# ft2232h-breakout.net
KiCad netlist of a schematic drawn in EAGLE
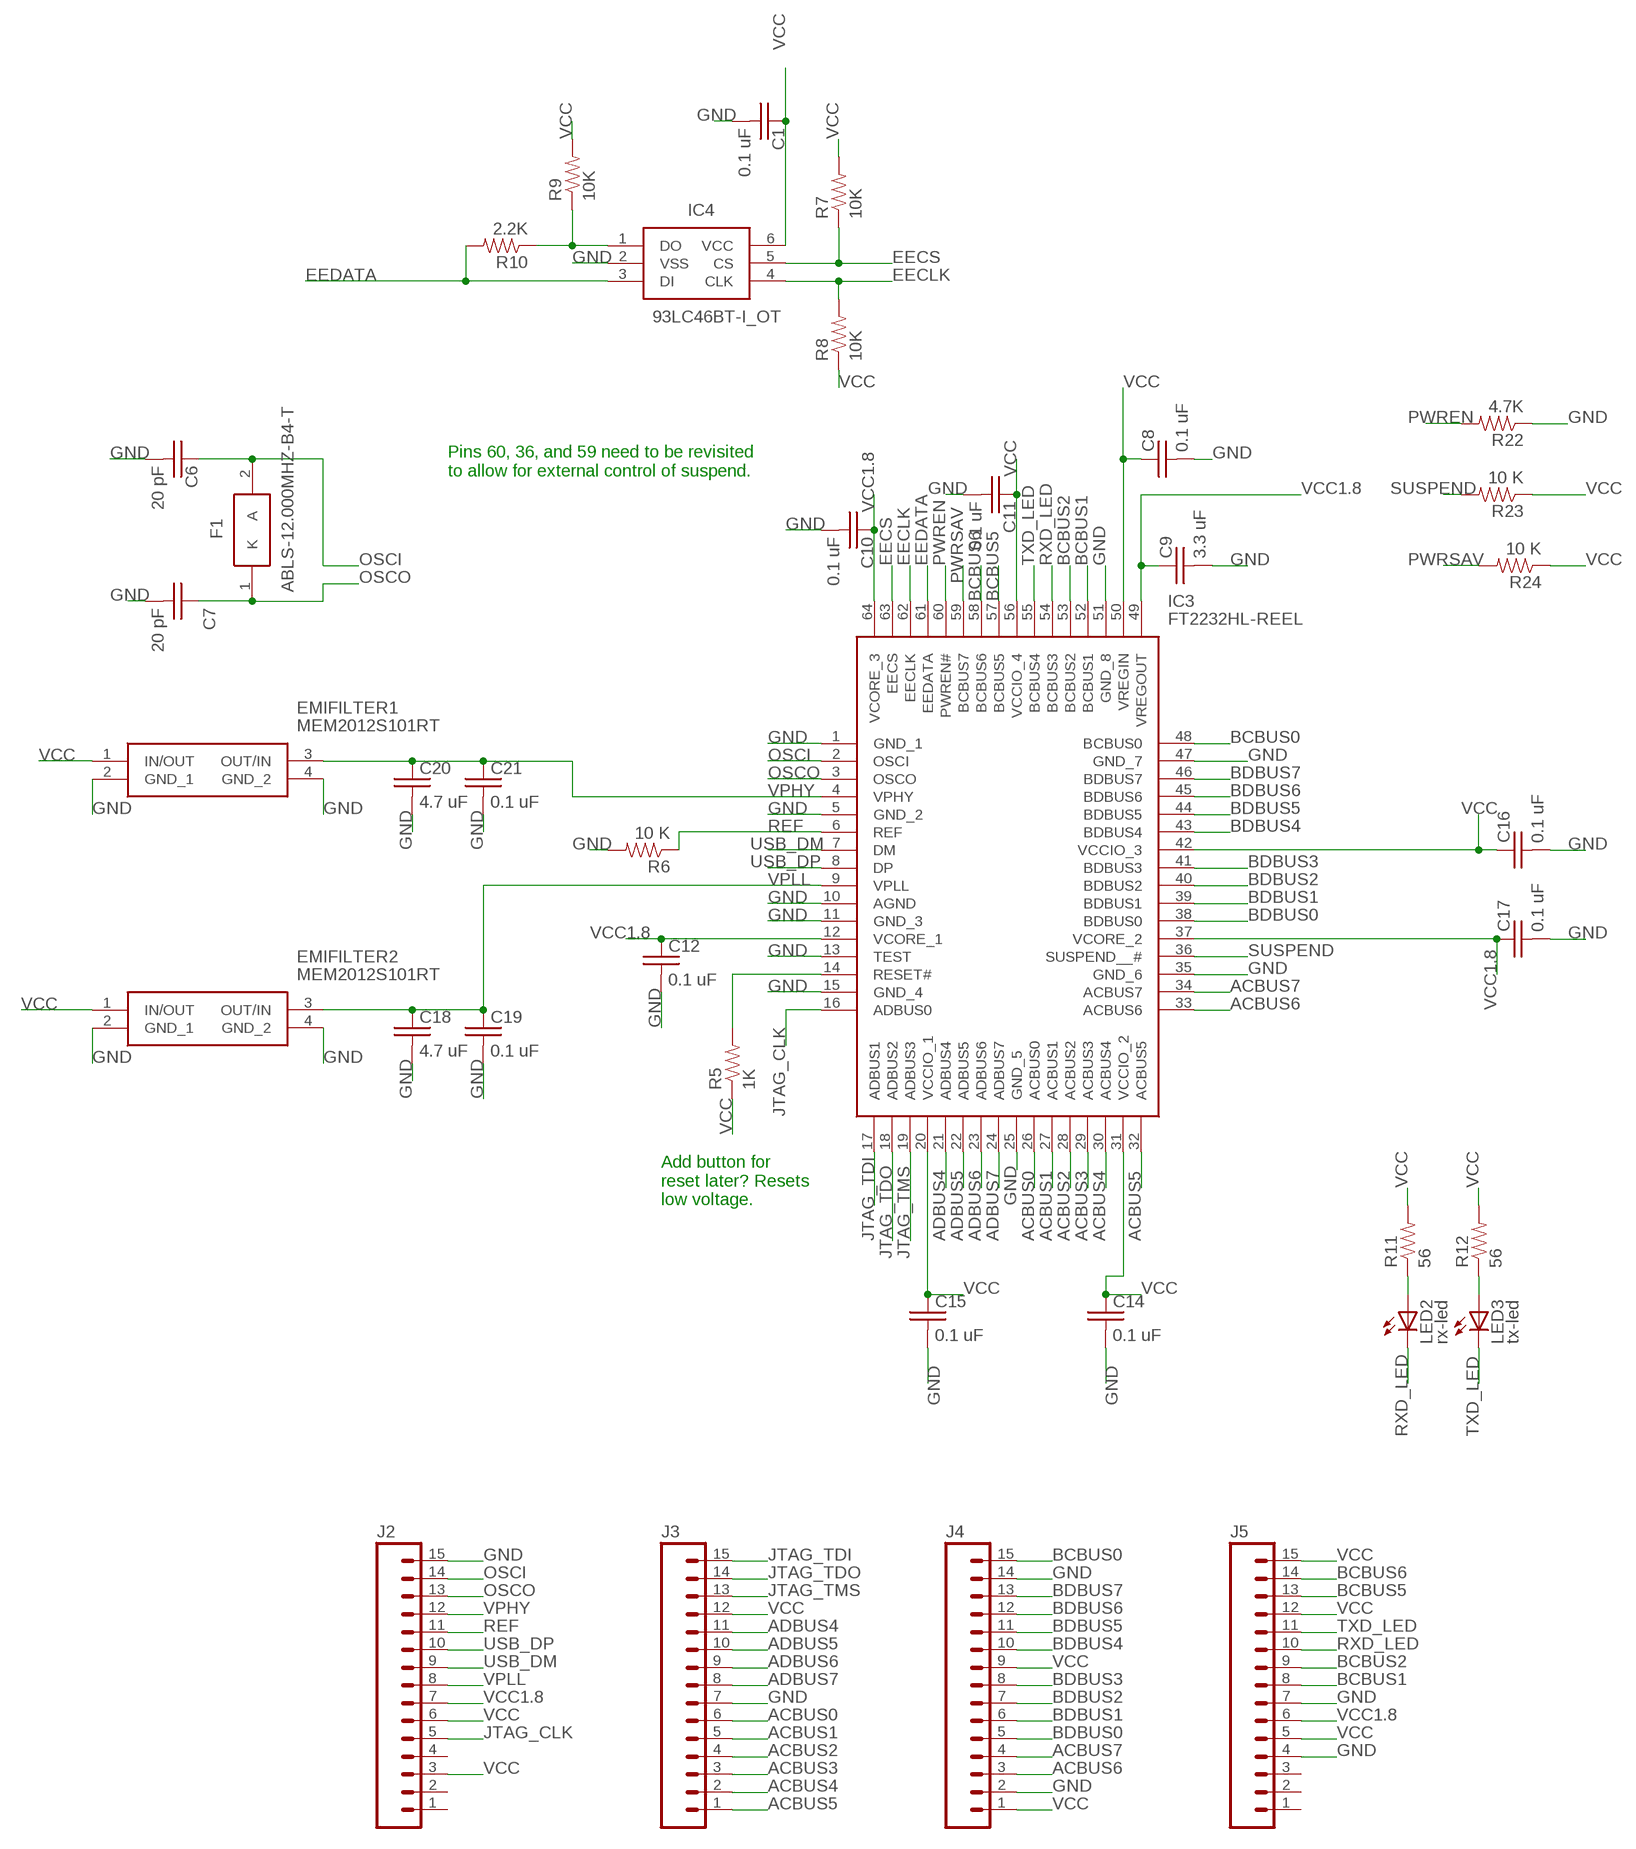
[diagram p0: schematic, sheet 1]
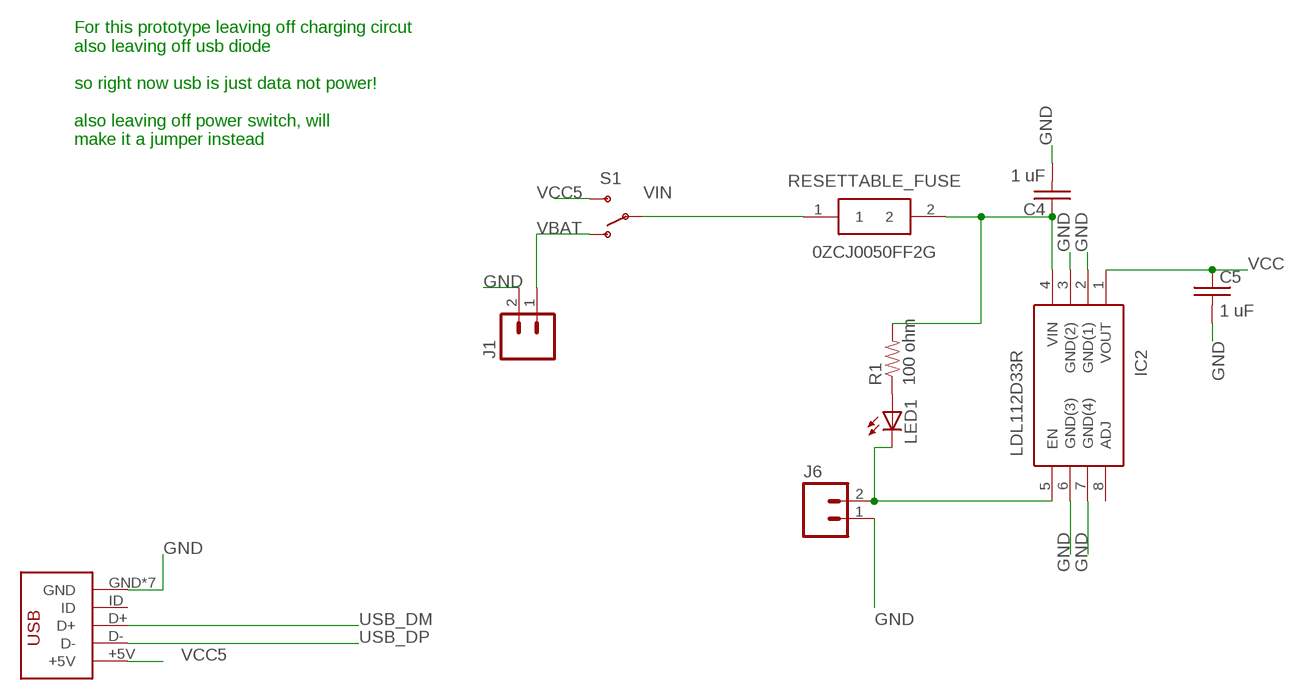
[diagram p1: schematic, sheet 2]

(export (version "E")
  (design (tool "Eeschema 10.0.6"))
  (components
    (comp (ref "C4")
      (value "1 uF")
      (footprint "eagle-import:C0805")
      (libsource (lib "eagle-import") (part "C-USC0805"))
    )
    (comp (ref "C5")
      (value "1 uF")
      (footprint "eagle-import:C0805")
      (libsource (lib "eagle-import") (part "C-USC0805"))
    )
    (comp (ref "IC2")
      (value "LDL112D33R")
      (footprint "eagle-import:SOIC127P600X175-8N")
      (libsource (lib "eagle-import") (part "LDL112D33R"))
    )
    (comp (ref "J1")
      (value "M02PTH")
      (footprint "eagle-import:1X02")
      (libsource (lib "eagle-import") (part "M02PTH"))
    )
    (comp (ref "J6")
      (value "M02PTH")
      (footprint "eagle-import:1X02")
      (libsource (lib "eagle-import") (part "M02PTH"))
    )
    (comp (ref "LED1")
      (value "LED3MM")
      (footprint "eagle-import:LED3MM")
      (libsource (lib "eagle-import") (part "LED3MM"))
    )
    (comp (ref "R1")
      (value "100 ohm")
      (footprint "eagle-import:AXIAL-0.3-KIT")
      (libsource (lib "eagle-import") (part "RESISTORKIT"))
    )
    (comp (ref "RESETTABLE_FUSE")
      (value "0ZCJ0050FF2G")
      (footprint "eagle-import:FUSC3216X55N")
      (libsource (lib "eagle-import") (part "0ZCJ0050FF2G"))
    )
    (comp (ref "S1")
      (value "SWITCH-SPSTPTH")
      (footprint "eagle-import:SWITCH-SPDT")
      (libsource (lib "eagle-import") (part "SWITCH-SPSTPTH"))
    )
    (comp (ref "U$2")
      (value "DX4R005JJ2DX4R005JJ2")
      (footprint "eagle-import:DX4R005JJ2")
      (libsource (lib "eagle-import") (part "DX4R005JJ2DX4R005JJ2"))
    )
    (comp (ref "C1")
      (value "0.1 uF")
      (footprint "eagle-import:C0805")
      (libsource (lib "eagle-import") (part "C-USC0805"))
    )
    (comp (ref "C6")
      (value "20 pF")
      (footprint "eagle-import:C0805")
      (libsource (lib "eagle-import") (part "C-USC0805"))
    )
    (comp (ref "C7")
      (value "20 pF")
      (footprint "eagle-import:C0805")
      (libsource (lib "eagle-import") (part "C-USC0805"))
    )
    (comp (ref "C8")
      (value "0.1 uF")
      (footprint "eagle-import:C0805")
      (libsource (lib "eagle-import") (part "C-USC0805"))
    )
    (comp (ref "C9")
      (value "3.3 uF")
      (footprint "eagle-import:C0805")
      (libsource (lib "eagle-import") (part "C-USC0805"))
    )
    (comp (ref "C10")
      (value "0.1 uF")
      (footprint "eagle-import:C0805")
      (libsource (lib "eagle-import") (part "C-USC0805"))
    )
    (comp (ref "C11")
      (value "0.1 uF")
      (footprint "eagle-import:C0805")
      (libsource (lib "eagle-import") (part "C-USC0805"))
    )
    (comp (ref "C12")
      (value "0.1 uF")
      (footprint "eagle-import:C0805")
      (libsource (lib "eagle-import") (part "C-USC0805"))
    )
    (comp (ref "C14")
      (value "0.1 uF")
      (footprint "eagle-import:C0805")
      (libsource (lib "eagle-import") (part "C-USC0805"))
    )
    (comp (ref "C15")
      (value "0.1 uF")
      (footprint "eagle-import:C0805")
      (libsource (lib "eagle-import") (part "C-USC0805"))
    )
    (comp (ref "C16")
      (value "0.1 uF")
      (footprint "eagle-import:C0805")
      (libsource (lib "eagle-import") (part "C-USC0805"))
    )
    (comp (ref "C17")
      (value "0.1 uF")
      (footprint "eagle-import:C0805")
      (libsource (lib "eagle-import") (part "C-USC0805"))
    )
    (comp (ref "C18")
      (value "4.7 uF")
      (footprint "eagle-import:C0805")
      (libsource (lib "eagle-import") (part "C-USC0805"))
    )
    (comp (ref "C19")
      (value "0.1 uF")
      (footprint "eagle-import:C0805")
      (libsource (lib "eagle-import") (part "C-USC0805"))
    )
    (comp (ref "C20")
      (value "4.7 uF")
      (footprint "eagle-import:C0805")
      (libsource (lib "eagle-import") (part "C-USC0805"))
    )
    (comp (ref "C21")
      (value "0.1 uF")
      (footprint "eagle-import:C0805")
      (libsource (lib "eagle-import") (part "C-USC0805"))
    )
    (comp (ref "EMIFILTER1")
      (value "MEM2012S101RT")
      (footprint "eagle-import:MEM2012S101RT")
      (libsource (lib "eagle-import") (part "MEM2012S101RT"))
    )
    (comp (ref "EMIFILTER2")
      (value "MEM2012S101RT")
      (footprint "eagle-import:MEM2012S101RT")
      (libsource (lib "eagle-import") (part "MEM2012S101RT"))
    )
    (comp (ref "F1")
      (value "ABLS-12.000MHZ-B4-T")
      (footprint "eagle-import:HC_49US-(AT49)_1")
      (fields
        (field (name "MOUSER_PART_NUMBER") "815-ABLS-12.0M-T")
        (field (name "RS_PART_NUMBER") "1710207")
      )
      (libsource (lib "eagle-import") (part "ABLS-12.000MHZ-B4-T"))
    )
    (comp (ref "IC3")
      (value "FT2232HL-REEL")
      (footprint "eagle-import:QFP50P1200X1200X160-64N")
      (fields (field (name "MOUSER_PART_NUMBER") "895-FT2232HL"))
      (libsource (lib "eagle-import") (part "FT2232HL-REEL"))
    )
    (comp (ref "IC4")
      (value "93LC46BT-I_OT")
      (footprint "eagle-import:SOT95P270X145-6N")
      (fields
        (field (name "MANUFACTURER_PART_NUMBER") "93LC46BT-I/OT")
        (field (name "MOUSER_PART_NUMBER") "579-93LC46BT-I/OT")
      )
      (libsource (lib "eagle-import") (part "93LC46BT-I_OT"))
    )
    (comp (ref "J2")
      (value "M15")
      (footprint "eagle-import:1X15")
      (libsource (lib "eagle-import") (part "M15"))
    )
    (comp (ref "J3")
      (value "M15")
      (footprint "eagle-import:1X15")
      (libsource (lib "eagle-import") (part "M15"))
    )
    (comp (ref "J4")
      (value "M15")
      (footprint "eagle-import:1X15")
      (libsource (lib "eagle-import") (part "M15"))
    )
    (comp (ref "J5")
      (value "M15")
      (footprint "eagle-import:1X15")
      (libsource (lib "eagle-import") (part "M15"))
    )
    (comp (ref "LED2")
      (value "rx-led")
      (footprint "eagle-import:LED3MM")
      (libsource (lib "eagle-import") (part "LED3MM"))
    )
    (comp (ref "LED3")
      (value "tx-led")
      (footprint "eagle-import:LED3MM")
      (libsource (lib "eagle-import") (part "LED3MM"))
    )
    (comp (ref "R5")
      (value "1K")
      (footprint "eagle-import:0805")
      (libsource (lib "eagle-import") (part "RESISTOR0805-RES"))
    )
    (comp (ref "R6")
      (value "10 K")
      (footprint "eagle-import:0805")
      (libsource (lib "eagle-import") (part "RESISTOR0805-RES"))
    )
    (comp (ref "R7")
      (value "10K")
      (footprint "eagle-import:0805")
      (libsource (lib "eagle-import") (part "RESISTOR0805-RES"))
    )
    (comp (ref "R8")
      (value "10K")
      (footprint "eagle-import:0805")
      (libsource (lib "eagle-import") (part "RESISTOR0805-RES"))
    )
    (comp (ref "R9")
      (value "10K")
      (footprint "eagle-import:0805")
      (libsource (lib "eagle-import") (part "RESISTOR0805-RES"))
    )
    (comp (ref "R10")
      (value "2.2K")
      (footprint "eagle-import:0805")
      (libsource (lib "eagle-import") (part "RESISTOR0805-RES"))
    )
    (comp (ref "R11")
      (value "56")
      (footprint "eagle-import:0805")
      (libsource (lib "eagle-import") (part "RESISTOR0805-RES"))
    )
    (comp (ref "R12")
      (value "56")
      (footprint "eagle-import:0805")
      (libsource (lib "eagle-import") (part "RESISTOR0805-RES"))
    )
    (comp (ref "R22")
      (value "4.7K")
      (footprint "eagle-import:0805")
      (libsource (lib "eagle-import") (part "RESISTOR0805-RES"))
    )
    (comp (ref "R23")
      (value "10 K")
      (footprint "eagle-import:0805")
      (libsource (lib "eagle-import") (part "RESISTOR0805-RES"))
    )
    (comp (ref "R24")
      (value "10 K")
      (footprint "eagle-import:0805")
      (libsource (lib "eagle-import") (part "RESISTOR0805-RES"))
    )
  )
  (nets
    (net (code "1") (name "ACBUS0") (class "Default")
      (node (ref "IC3") (pin "26") (pinfunction "ACBUS0_26") (pintype "bidirectional"))
      (node (ref "J3") (pin "6") (pinfunction "6_6") (pintype "passive"))
    )
    (net (code "2") (name "ACBUS1") (class "Default")
      (node (ref "IC3") (pin "27") (pinfunction "ACBUS1_27") (pintype "bidirectional"))
      (node (ref "J3") (pin "5") (pinfunction "5_5") (pintype "passive"))
    )
    (net (code "3") (name "ACBUS2") (class "Default")
      (node (ref "IC3") (pin "28") (pinfunction "ACBUS2_28") (pintype "bidirectional"))
      (node (ref "J3") (pin "4") (pinfunction "4_4") (pintype "passive"))
    )
    (net (code "4") (name "ACBUS3") (class "Default")
      (node (ref "IC3") (pin "29") (pinfunction "ACBUS3_29") (pintype "bidirectional"))
      (node (ref "J3") (pin "3") (pinfunction "3_3") (pintype "passive"))
    )
    (net (code "5") (name "ACBUS4") (class "Default")
      (node (ref "IC3") (pin "30") (pinfunction "ACBUS4_30") (pintype "bidirectional"))
      (node (ref "J3") (pin "2") (pinfunction "2_2") (pintype "passive"))
    )
    (net (code "6") (name "ACBUS5") (class "Default")
      (node (ref "IC3") (pin "32") (pinfunction "ACBUS5_32") (pintype "bidirectional"))
      (node (ref "J3") (pin "1") (pinfunction "1_1") (pintype "passive"))
    )
    (net (code "7") (name "ACBUS6") (class "Default")
      (node (ref "IC3") (pin "33") (pinfunction "ACBUS6_33") (pintype "bidirectional"))
      (node (ref "J4") (pin "3") (pinfunction "3_3") (pintype "passive"))
    )
    (net (code "8") (name "ACBUS7") (class "Default")
      (node (ref "IC3") (pin "34") (pinfunction "ACBUS7_34") (pintype "bidirectional"))
      (node (ref "J4") (pin "4") (pinfunction "4_4") (pintype "passive"))
    )
    (net (code "9") (name "ADBUS4") (class "Default")
      (node (ref "IC3") (pin "21") (pinfunction "ADBUS4_21") (pintype "bidirectional"))
      (node (ref "J3") (pin "11") (pinfunction "11_11") (pintype "passive"))
    )
    (net (code "10") (name "ADBUS5") (class "Default")
      (node (ref "IC3") (pin "22") (pinfunction "ADBUS5_22") (pintype "bidirectional"))
      (node (ref "J3") (pin "10") (pinfunction "10_10") (pintype "passive"))
    )
    (net (code "11") (name "ADBUS6") (class "Default")
      (node (ref "IC3") (pin "23") (pinfunction "ADBUS6_23") (pintype "bidirectional"))
      (node (ref "J3") (pin "9") (pinfunction "9_9") (pintype "passive"))
    )
    (net (code "12") (name "ADBUS7") (class "Default")
      (node (ref "IC3") (pin "24") (pinfunction "ADBUS7_24") (pintype "bidirectional"))
      (node (ref "J3") (pin "8") (pinfunction "8_8") (pintype "passive"))
    )
    (net (code "13") (name "BCBUS0") (class "Default")
      (node (ref "IC3") (pin "48") (pinfunction "BCBUS0_48") (pintype "bidirectional"))
      (node (ref "J4") (pin "15") (pinfunction "15_15") (pintype "passive"))
    )
    (net (code "14") (name "BCBUS1") (class "Default")
      (node (ref "IC3") (pin "52") (pinfunction "BCBUS1_52") (pintype "bidirectional"))
      (node (ref "J5") (pin "8") (pinfunction "8_8") (pintype "passive"))
    )
    (net (code "15") (name "BCBUS2") (class "Default")
      (node (ref "IC3") (pin "53") (pinfunction "BCBUS2_53") (pintype "bidirectional"))
      (node (ref "J5") (pin "9") (pinfunction "9_9") (pintype "passive"))
    )
    (net (code "16") (name "BCBUS5") (class "Default")
      (node (ref "IC3") (pin "57") (pinfunction "BCBUS5_57") (pintype "bidirectional"))
      (node (ref "J5") (pin "13") (pinfunction "13_13") (pintype "passive"))
    )
    (net (code "17") (name "BCBUS6") (class "Default")
      (node (ref "IC3") (pin "58") (pinfunction "BCBUS6_58") (pintype "bidirectional"))
      (node (ref "J5") (pin "14") (pinfunction "14_14") (pintype "passive"))
    )
    (net (code "18") (name "BDBUS0") (class "Default")
      (node (ref "IC3") (pin "38") (pinfunction "BDBUS0_38") (pintype "bidirectional"))
      (node (ref "J4") (pin "5") (pinfunction "5_5") (pintype "passive"))
    )
    (net (code "19") (name "BDBUS1") (class "Default")
      (node (ref "IC3") (pin "39") (pinfunction "BDBUS1_39") (pintype "bidirectional"))
      (node (ref "J4") (pin "6") (pinfunction "6_6") (pintype "passive"))
    )
    (net (code "20") (name "BDBUS2") (class "Default")
      (node (ref "IC3") (pin "40") (pinfunction "BDBUS2_40") (pintype "bidirectional"))
      (node (ref "J4") (pin "7") (pinfunction "7_7") (pintype "passive"))
    )
    (net (code "21") (name "BDBUS3") (class "Default")
      (node (ref "IC3") (pin "41") (pinfunction "BDBUS3_41") (pintype "bidirectional"))
      (node (ref "J4") (pin "8") (pinfunction "8_8") (pintype "passive"))
    )
    (net (code "22") (name "BDBUS4") (class "Default")
      (node (ref "IC3") (pin "43") (pinfunction "BDBUS4_43") (pintype "bidirectional"))
      (node (ref "J4") (pin "10") (pinfunction "10_10") (pintype "passive"))
    )
    (net (code "23") (name "BDBUS5") (class "Default")
      (node (ref "IC3") (pin "44") (pinfunction "BDBUS5_44") (pintype "bidirectional"))
      (node (ref "J4") (pin "11") (pinfunction "11_11") (pintype "passive"))
    )
    (net (code "24") (name "BDBUS6") (class "Default")
      (node (ref "IC3") (pin "45") (pinfunction "BDBUS6_45") (pintype "bidirectional"))
      (node (ref "J4") (pin "12") (pinfunction "12_12") (pintype "passive"))
    )
    (net (code "25") (name "BDBUS7") (class "Default")
      (node (ref "IC3") (pin "46") (pinfunction "BDBUS7_46") (pintype "bidirectional"))
      (node (ref "J4") (pin "13") (pinfunction "13_13") (pintype "passive"))
    )
    (net (code "26") (name "EECLK") (class "Default")
      (node (ref "IC3") (pin "62") (pinfunction "EECLK_62") (pintype "bidirectional"))
      (node (ref "IC4") (pin "4") (pinfunction "CLK_4") (pintype "input"))
      (node (ref "R8") (pin "2") (pinfunction "2_2") (pintype "passive"))
    )
    (net (code "27") (name "EECS") (class "Default")
      (node (ref "IC3") (pin "63") (pinfunction "EECS_63") (pintype "bidirectional"))
      (node (ref "IC4") (pin "5") (pinfunction "CS_5") (pintype "input"))
      (node (ref "R7") (pin "1") (pinfunction "1_1") (pintype "passive"))
    )
    (net (code "28") (name "EEDATA") (class "Default")
      (node (ref "IC3") (pin "61") (pinfunction "EEDATA_61") (pintype "bidirectional"))
      (node (ref "IC4") (pin "3") (pinfunction "DI_3") (pintype "bidirectional"))
      (node (ref "R10") (pin "2") (pinfunction "2_2") (pintype "passive"))
    )
    (net (code "29") (name "GND") (class "Default")
      (node (ref "C1") (pin "2") (pinfunction "2_2") (pintype "passive"))
      (node (ref "C10") (pin "2") (pinfunction "2_2") (pintype "passive"))
      (node (ref "C11") (pin "2") (pinfunction "2_2") (pintype "passive"))
      (node (ref "C12") (pin "2") (pinfunction "2_2") (pintype "passive"))
      (node (ref "C14") (pin "2") (pinfunction "2_2") (pintype "passive"))
      (node (ref "C15") (pin "2") (pinfunction "2_2") (pintype "passive"))
      (node (ref "C16") (pin "2") (pinfunction "2_2") (pintype "passive"))
      (node (ref "C17") (pin "2") (pinfunction "2_2") (pintype "passive"))
      (node (ref "C18") (pin "2") (pinfunction "2_2") (pintype "passive"))
      (node (ref "C19") (pin "2") (pinfunction "2_2") (pintype "passive"))
      (node (ref "C20") (pin "2") (pinfunction "2_2") (pintype "passive"))
      (node (ref "C21") (pin "2") (pinfunction "2_2") (pintype "passive"))
      (node (ref "C4") (pin "2") (pinfunction "2_2") (pintype "passive"))
      (node (ref "C5") (pin "2") (pinfunction "2_2") (pintype "passive"))
      (node (ref "C6") (pin "2") (pinfunction "2_2") (pintype "passive"))
      (node (ref "C7") (pin "2") (pinfunction "2_2") (pintype "passive"))
      (node (ref "C8") (pin "2") (pinfunction "2_2") (pintype "passive"))
      (node (ref "C9") (pin "2") (pinfunction "2_2") (pintype "passive"))
      (node (ref "EMIFILTER1") (pin "2") (pinfunction "GND_1_2") (pintype "bidirectional"))
      (node (ref "EMIFILTER1") (pin "4") (pinfunction "GND_2_4") (pintype "bidirectional"))
      (node (ref "EMIFILTER2") (pin "2") (pinfunction "GND_1_2") (pintype "bidirectional"))
      (node (ref "EMIFILTER2") (pin "4") (pinfunction "GND_2_4") (pintype "bidirectional"))
      (node (ref "IC2") (pin "2") (pinfunction "GND(1)_2") (pintype "bidirectional"))
      (node (ref "IC2") (pin "3") (pinfunction "GND(2)_3") (pintype "bidirectional"))
      (node (ref "IC2") (pin "6") (pinfunction "GND(3)_6") (pintype "bidirectional"))
      (node (ref "IC2") (pin "7") (pinfunction "GND(4)_7") (pintype "bidirectional"))
      (node (ref "IC3") (pin "1") (pinfunction "GND_1_1") (pintype "bidirectional"))
      (node (ref "IC3") (pin "10") (pinfunction "AGND_10") (pintype "bidirectional"))
      (node (ref "IC3") (pin "11") (pinfunction "GND_3_11") (pintype "bidirectional"))
      (node (ref "IC3") (pin "13") (pinfunction "TEST_13") (pintype "bidirectional"))
      (node (ref "IC3") (pin "15") (pinfunction "GND_4_15") (pintype "bidirectional"))
      (node (ref "IC3") (pin "25") (pinfunction "GND_5_25") (pintype "bidirectional"))
      (node (ref "IC3") (pin "35") (pinfunction "GND_6_35") (pintype "bidirectional"))
      (node (ref "IC3") (pin "47") (pinfunction "GND_7_47") (pintype "bidirectional"))
      (node (ref "IC3") (pin "5") (pinfunction "GND_2_5") (pintype "bidirectional"))
      (node (ref "IC3") (pin "51") (pinfunction "GND_8_51") (pintype "bidirectional"))
      (node (ref "IC4") (pin "2") (pinfunction "VSS_2") (pintype "power_in"))
      (node (ref "J1") (pin "2") (pinfunction "2_2") (pintype "passive"))
      (node (ref "J2") (pin "15") (pinfunction "15_15") (pintype "passive"))
      (node (ref "J3") (pin "7") (pinfunction "7_7") (pintype "passive"))
      (node (ref "J4") (pin "14") (pinfunction "14_14") (pintype "passive"))
      (node (ref "J4") (pin "2") (pinfunction "2_2") (pintype "passive"))
      (node (ref "J5") (pin "4") (pinfunction "4_4") (pintype "passive"))
      (node (ref "J5") (pin "7") (pinfunction "7_7") (pintype "passive"))
      (node (ref "J6") (pin "1") (pinfunction "1_1") (pintype "passive"))
      (node (ref "R22") (pin "1") (pinfunction "1_1") (pintype "passive"))
      (node (ref "R6") (pin "2") (pinfunction "2_2") (pintype "passive"))
      (node (ref "U$2") (pin "GND") (pinfunction "GND_GND") (pintype "bidirectional"))
      (node (ref "U$2") (pin "P$10") (pinfunction "GND_P$10") (pintype "bidirectional"))
      (node (ref "U$2") (pin "P$11") (pinfunction "GND_P$11") (pintype "bidirectional"))
      (node (ref "U$2") (pin "P$6") (pinfunction "GND_P$6") (pintype "bidirectional"))
      (node (ref "U$2") (pin "P$7") (pinfunction "GND_P$7") (pintype "bidirectional"))
      (node (ref "U$2") (pin "P$8") (pinfunction "GND_P$8") (pintype "bidirectional"))
      (node (ref "U$2") (pin "P$9") (pinfunction "GND_P$9") (pintype "bidirectional"))
    )
    (net (code "30") (name "JTAG_CLK") (class "Default")
      (node (ref "IC3") (pin "16") (pinfunction "ADBUS0_16") (pintype "bidirectional"))
      (node (ref "J2") (pin "5") (pinfunction "5_5") (pintype "passive"))
    )
    (net (code "31") (name "JTAG_TDI") (class "Default")
      (node (ref "IC3") (pin "17") (pinfunction "ADBUS1_17") (pintype "bidirectional"))
      (node (ref "J3") (pin "15") (pinfunction "15_15") (pintype "passive"))
    )
    (net (code "32") (name "JTAG_TDO") (class "Default")
      (node (ref "IC3") (pin "18") (pinfunction "ADBUS2_18") (pintype "bidirectional"))
      (node (ref "J3") (pin "14") (pinfunction "14_14") (pintype "passive"))
    )
    (net (code "33") (name "JTAG_TMS") (class "Default")
      (node (ref "IC3") (pin "19") (pinfunction "ADBUS3_19") (pintype "bidirectional"))
      (node (ref "J3") (pin "13") (pinfunction "13_13") (pintype "passive"))
    )
    (net (code "34") (name "Net-(IC2-EN)") (class "Default")
      (node (ref "IC2") (pin "5") (pinfunction "EN_5") (pintype "bidirectional"))
      (node (ref "J6") (pin "2") (pinfunction "2_2") (pintype "passive"))
      (node (ref "LED1") (pin "K") (pinfunction "C_K") (pintype "output"))
    )
    (net (code "35") (name "Net-(IC2-VIN)") (class "Default")
      (node (ref "C4") (pin "1") (pinfunction "1_1") (pintype "passive"))
      (node (ref "IC2") (pin "4") (pinfunction "VIN_4") (pintype "bidirectional"))
      (node (ref "R1") (pin "P$2") (pinfunction "2_P$2") (pintype "passive"))
      (node (ref "RESETTABLE_FUSE") (pin "2") (pinfunction "2_2") (pintype "passive"))
    )
    (net (code "36") (name "Net-(IC3-RESET#)") (class "Default")
      (node (ref "IC3") (pin "14") (pinfunction "RESET#_14") (pintype "bidirectional"))
      (node (ref "R5") (pin "2") (pinfunction "2_2") (pintype "passive"))
    )
    (net (code "37") (name "Net-(IC4-DO)") (class "Default")
      (node (ref "IC4") (pin "1") (pinfunction "DO_1") (pintype "bidirectional"))
      (node (ref "R10") (pin "1") (pinfunction "1_1") (pintype "passive"))
      (node (ref "R9") (pin "1") (pinfunction "1_1") (pintype "passive"))
    )
    (net (code "38") (name "Net-(LED2-PadA)") (class "Default")
      (node (ref "LED2") (pin "A") (pinfunction "A_A") (pintype "input"))
      (node (ref "R11") (pin "1") (pinfunction "1_1") (pintype "passive"))
    )
    (net (code "39") (name "Net-(LED3-PadA)") (class "Default")
      (node (ref "LED3") (pin "A") (pinfunction "A_A") (pintype "input"))
      (node (ref "R12") (pin "1") (pinfunction "1_1") (pintype "passive"))
    )
    (net (code "40") (name "Net-(R1-1)") (class "Default")
      (node (ref "LED1") (pin "A") (pinfunction "A_A") (pintype "input"))
      (node (ref "R1") (pin "P$1") (pinfunction "1_P$1") (pintype "passive"))
    )
    (net (code "41") (name "OSCI") (class "Default")
      (node (ref "C6") (pin "1") (pinfunction "1_1") (pintype "passive"))
      (node (ref "F1") (pin "2") (pinfunction "A_2") (pintype "bidirectional"))
      (node (ref "IC3") (pin "2") (pinfunction "OSCI_2") (pintype "bidirectional"))
      (node (ref "J2") (pin "14") (pinfunction "14_14") (pintype "passive"))
    )
    (net (code "42") (name "OSCO") (class "Default")
      (node (ref "C7") (pin "1") (pinfunction "1_1") (pintype "passive"))
      (node (ref "F1") (pin "1") (pinfunction "K_1") (pintype "bidirectional"))
      (node (ref "IC3") (pin "3") (pinfunction "OSCO_3") (pintype "bidirectional"))
      (node (ref "J2") (pin "13") (pinfunction "13_13") (pintype "passive"))
    )
    (net (code "43") (name "PWREN") (class "Default")
      (node (ref "IC3") (pin "60") (pinfunction "PWREN#_60") (pintype "bidirectional"))
      (node (ref "R22") (pin "2") (pinfunction "2_2") (pintype "passive"))
    )
    (net (code "44") (name "PWRSAV") (class "Default")
      (node (ref "IC3") (pin "59") (pinfunction "BCBUS7_59") (pintype "bidirectional"))
      (node (ref "R24") (pin "2") (pinfunction "2_2") (pintype "passive"))
    )
    (net (code "45") (name "REF") (class "Default")
      (node (ref "IC3") (pin "6") (pinfunction "REF_6") (pintype "bidirectional"))
      (node (ref "J2") (pin "11") (pinfunction "11_11") (pintype "passive"))
      (node (ref "R6") (pin "1") (pinfunction "1_1") (pintype "passive"))
    )
    (net (code "46") (name "RXD_LED") (class "Default")
      (node (ref "IC3") (pin "54") (pinfunction "BCBUS3_54") (pintype "bidirectional"))
      (node (ref "J5") (pin "10") (pinfunction "10_10") (pintype "passive"))
      (node (ref "LED2") (pin "K") (pinfunction "C_K") (pintype "output"))
    )
    (net (code "47") (name "SUSPEND") (class "Default")
      (node (ref "IC3") (pin "36") (pinfunction "SUSPEND__#_36") (pintype "bidirectional"))
      (node (ref "R23") (pin "2") (pinfunction "2_2") (pintype "passive"))
    )
    (net (code "48") (name "TXD_LED") (class "Default")
      (node (ref "IC3") (pin "55") (pinfunction "BCBUS4_55") (pintype "bidirectional"))
      (node (ref "J5") (pin "11") (pinfunction "11_11") (pintype "passive"))
      (node (ref "LED3") (pin "K") (pinfunction "C_K") (pintype "output"))
    )
    (net (code "49") (name "USB_DM") (class "Default")
      (node (ref "IC3") (pin "7") (pinfunction "DM_7") (pintype "bidirectional"))
      (node (ref "J2") (pin "9") (pinfunction "9_9") (pintype "passive"))
      (node (ref "U$2") (pin "D+") (pinfunction "D+_D+") (pintype "bidirectional"))
    )
    (net (code "50") (name "USB_DP") (class "Default")
      (node (ref "IC3") (pin "8") (pinfunction "DP_8") (pintype "bidirectional"))
      (node (ref "J2") (pin "10") (pinfunction "10_10") (pintype "passive"))
      (node (ref "U$2") (pin "D-") (pinfunction "D-_D-") (pintype "bidirectional"))
    )
    (net (code "51") (name "VBAT") (class "Default")
      (node (ref "J1") (pin "1") (pinfunction "1_1") (pintype "passive"))
      (node (ref "S1") (pin "1") (pinfunction "O_1") (pintype "passive"))
    )
    (net (code "52") (name "VCC") (class "Default")
      (node (ref "C1") (pin "1") (pinfunction "1_1") (pintype "passive"))
      (node (ref "C11") (pin "1") (pinfunction "1_1") (pintype "passive"))
      (node (ref "C14") (pin "1") (pinfunction "1_1") (pintype "passive"))
      (node (ref "C15") (pin "1") (pinfunction "1_1") (pintype "passive"))
      (node (ref "C16") (pin "1") (pinfunction "1_1") (pintype "passive"))
      (node (ref "C5") (pin "1") (pinfunction "1_1") (pintype "passive"))
      (node (ref "C8") (pin "1") (pinfunction "1_1") (pintype "passive"))
      (node (ref "EMIFILTER1") (pin "1") (pinfunction "IN/OUT_1") (pintype "bidirectional"))
      (node (ref "EMIFILTER2") (pin "1") (pinfunction "IN/OUT_1") (pintype "bidirectional"))
      (node (ref "IC2") (pin "1") (pinfunction "VOUT_1") (pintype "bidirectional"))
      (node (ref "IC3") (pin "20") (pinfunction "VCCIO_1_20") (pintype "bidirectional"))
      (node (ref "IC3") (pin "31") (pinfunction "VCCIO_2_31") (pintype "bidirectional"))
      (node (ref "IC3") (pin "42") (pinfunction "VCCIO_3_42") (pintype "bidirectional"))
      (node (ref "IC3") (pin "50") (pinfunction "VREGIN_50") (pintype "bidirectional"))
      (node (ref "IC3") (pin "56") (pinfunction "VCCIO_4_56") (pintype "bidirectional"))
      (node (ref "IC4") (pin "6") (pinfunction "VCC_6") (pintype "power_in"))
      (node (ref "J2") (pin "3") (pinfunction "3_3") (pintype "passive"))
      (node (ref "J2") (pin "6") (pinfunction "6_6") (pintype "passive"))
      (node (ref "J3") (pin "12") (pinfunction "12_12") (pintype "passive"))
      (node (ref "J4") (pin "1") (pinfunction "1_1") (pintype "passive"))
      (node (ref "J4") (pin "9") (pinfunction "9_9") (pintype "passive"))
      (node (ref "J5") (pin "12") (pinfunction "12_12") (pintype "passive"))
      (node (ref "J5") (pin "15") (pinfunction "15_15") (pintype "passive"))
      (node (ref "J5") (pin "5") (pinfunction "5_5") (pintype "passive"))
      (node (ref "R11") (pin "2") (pinfunction "2_2") (pintype "passive"))
      (node (ref "R12") (pin "2") (pinfunction "2_2") (pintype "passive"))
      (node (ref "R23") (pin "1") (pinfunction "1_1") (pintype "passive"))
      (node (ref "R24") (pin "1") (pinfunction "1_1") (pintype "passive"))
      (node (ref "R5") (pin "1") (pinfunction "1_1") (pintype "passive"))
      (node (ref "R7") (pin "2") (pinfunction "2_2") (pintype "passive"))
      (node (ref "R8") (pin "1") (pinfunction "1_1") (pintype "passive"))
      (node (ref "R9") (pin "2") (pinfunction "2_2") (pintype "passive"))
    )
    (net (code "53") (name "VCC1.8") (class "Default")
      (node (ref "C10") (pin "1") (pinfunction "1_1") (pintype "passive"))
      (node (ref "C12") (pin "1") (pinfunction "1_1") (pintype "passive"))
      (node (ref "C17") (pin "1") (pinfunction "1_1") (pintype "passive"))
      (node (ref "C9") (pin "1") (pinfunction "1_1") (pintype "passive"))
      (node (ref "IC3") (pin "12") (pinfunction "VCORE_1_12") (pintype "bidirectional"))
      (node (ref "IC3") (pin "37") (pinfunction "VCORE_2_37") (pintype "bidirectional"))
      (node (ref "IC3") (pin "49") (pinfunction "VREGOUT_49") (pintype "bidirectional"))
      (node (ref "IC3") (pin "64") (pinfunction "VCORE_3_64") (pintype "bidirectional"))
      (node (ref "J2") (pin "7") (pinfunction "7_7") (pintype "passive"))
      (node (ref "J5") (pin "6") (pinfunction "6_6") (pintype "passive"))
    )
    (net (code "54") (name "VCC5") (class "Default")
      (node (ref "S1") (pin "3") (pinfunction "S_3") (pintype "passive"))
      (node (ref "U$2") (pin "+5V") (pinfunction "+5V_+5V") (pintype "bidirectional"))
    )
    (net (code "55") (name "VIN") (class "Default")
      (node (ref "RESETTABLE_FUSE") (pin "1") (pinfunction "1_1") (pintype "passive"))
      (node (ref "S1") (pin "2") (pinfunction "P_2") (pintype "passive"))
    )
    (net (code "56") (name "VPHY") (class "Default")
      (node (ref "C20") (pin "1") (pinfunction "1_1") (pintype "passive"))
      (node (ref "C21") (pin "1") (pinfunction "1_1") (pintype "passive"))
      (node (ref "EMIFILTER1") (pin "3") (pinfunction "OUT/IN_3") (pintype "bidirectional"))
      (node (ref "IC3") (pin "4") (pinfunction "VPHY_4") (pintype "bidirectional"))
      (node (ref "J2") (pin "12") (pinfunction "12_12") (pintype "passive"))
    )
    (net (code "57") (name "VPLL") (class "Default")
      (node (ref "C18") (pin "1") (pinfunction "1_1") (pintype "passive"))
      (node (ref "C19") (pin "1") (pinfunction "1_1") (pintype "passive"))
      (node (ref "EMIFILTER2") (pin "3") (pinfunction "OUT/IN_3") (pintype "bidirectional"))
      (node (ref "IC3") (pin "9") (pinfunction "VPLL_9") (pintype "bidirectional"))
      (node (ref "J2") (pin "8") (pinfunction "8_8") (pintype "passive"))
    )
    (net (code "58") (name "unconnected-(IC2-ADJ-Pad8)") (class "Default")
      (node (ref "IC2") (pin "8") (pinfunction "ADJ_8") (pintype "bidirectional"))
    )
    (net (code "59") (name "unconnected-(J2-Pad1)") (class "Default")
      (node (ref "J2") (pin "1") (pinfunction "1_1") (pintype "passive"))
    )
    (net (code "60") (name "unconnected-(J2-Pad2)") (class "Default")
      (node (ref "J2") (pin "2") (pinfunction "2_2") (pintype "passive"))
    )
    (net (code "61") (name "unconnected-(J2-Pad4)") (class "Default")
      (node (ref "J2") (pin "4") (pinfunction "4_4") (pintype "passive"))
    )
    (net (code "62") (name "unconnected-(J5-Pad1)") (class "Default")
      (node (ref "J5") (pin "1") (pinfunction "1_1") (pintype "passive"))
    )
    (net (code "63") (name "unconnected-(J5-Pad2)") (class "Default")
      (node (ref "J5") (pin "2") (pinfunction "2_2") (pintype "passive"))
    )
    (net (code "64") (name "unconnected-(J5-Pad3)") (class "Default")
      (node (ref "J5") (pin "3") (pinfunction "3_3") (pintype "passive"))
    )
    (net (code "65") (name "unconnected-(U$2-PadID)") (class "Default")
      (node (ref "U$2") (pin "ID") (pinfunction "ID_ID") (pintype "bidirectional"))
    )
  )
)
